# Driver.net
KiCad netlist of a schematic drawn in Altium Designer
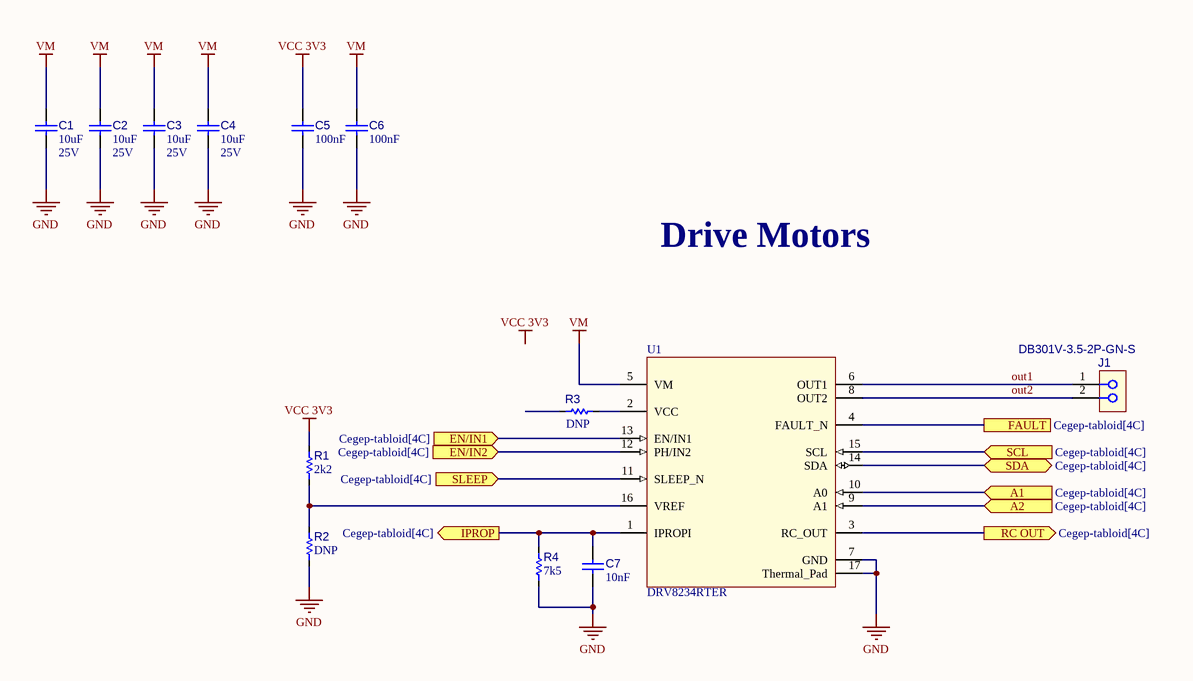
[diagram p0: Driver.SchDoc]

(export (version "E")
  (design (tool "Eeschema 10.0.6"))
  (components
    (comp (ref "C1")
      (value "10uF")
      (footprint "C_2012[0805]")
      (description "Capacitor type 1")
      (fields
        (field (name "TOLERANCE") "10%")
        (field (name "RATED VOLTAGE") "25V")
        (field (name "Comment") "CAP CER 10uF 25V X5R 0805")
      )
      (libsource (lib "243-436-MikoBus-DrvMot") (part "CAP020"))
    )
    (comp (ref "C2")
      (value "10uF")
      (footprint "C_2012[0805]")
      (description "Capacitor type 1")
      (fields
        (field (name "TOLERANCE") "10%")
        (field (name "RATED VOLTAGE") "25V")
        (field (name "Comment") "CAP CER 10uF 25V X5R 0805")
      )
      (libsource (lib "243-436-MikoBus-DrvMot") (part "CAP020"))
    )
    (comp (ref "C3")
      (value "10uF")
      (footprint "C_2012[0805]")
      (description "Capacitor type 1")
      (fields
        (field (name "TOLERANCE") "10%")
        (field (name "RATED VOLTAGE") "25V")
        (field (name "Comment") "CAP CER 10uF 25V X5R 0805")
      )
      (libsource (lib "243-436-MikoBus-DrvMot") (part "CAP020"))
    )
    (comp (ref "C4")
      (value "10uF")
      (footprint "C_2012[0805]")
      (description "Capacitor type 1")
      (fields
        (field (name "TOLERANCE") "10%")
        (field (name "RATED VOLTAGE") "25V")
        (field (name "Comment") "CAP CER 10uF 25V X5R 0805")
      )
      (libsource (lib "243-436-MikoBus-DrvMot") (part "CAP020"))
    )
    (comp (ref "C5")
      (value "100nF")
      (footprint "C_1005[0402]")
      (description "Capacitor type 1")
      (fields (field (name "TOLERANCE") "10%") (field (name "Comment") "CAP CER 100nF 50V 0402"))
      (libsource (lib "243-436-MikoBus-DrvMot") (part "CAP001"))
    )
    (comp (ref "C6")
      (value "100nF")
      (footprint "C_1005[0402]")
      (description "Capacitor type 1")
      (fields (field (name "TOLERANCE") "10%") (field (name "Comment") "CAP CER 100nF 50V 0402"))
      (libsource (lib "243-436-MikoBus-DrvMot") (part "CAP001"))
    )
    (comp (ref "C7")
      (value "10nF")
      (footprint "C_1005[0402]")
      (description "Capacitor type 1")
      (fields (field (name "TOLERANCE") "10%") (field (name "Comment") "CAP CER 10nF 50V X7R 0402"))
      (libsource (lib "243-436-MikoBus-DrvMot") (part "CAP017"))
    )
    (comp (ref "J1")
      (value "DB301V-3.5-2P-GN-S")
      (footprint "CONN_TERM_BLOCK_2POS_3mm5")
      (description "CONN TERM BLOCK 2POS 3.5mm pitch")
      (libsource (lib "TEP_243-AltiumLIB-Conn-TP-MH") (part "CONN-3MM5-2POS-TERM-BLOCK"))
    )
    (comp (ref "R1")
      (value "2k2")
      (footprint "R_1005[0402]")
      (description "Resistor type 1")
      (fields (field (name "TOLERANCE") "1%") (field (name "Comment") "Res 2k2 1% 0402"))
      (libsource (lib "243-436-MikoBus-DrvMot") (part "RES008"))
    )
    (comp (ref "R2")
      (value "DNP")
      (footprint "R_1005[0402]")
      (description "Resistor type 1")
      (fields (field (name "TOLERANCE") "1%") (field (name "Comment") "Res 2k2 1% 0402"))
      (libsource (lib "243-436-MikoBus-DrvMot") (part "RES008"))
    )
    (comp (ref "R3")
      (value "DNP")
      (footprint "R_1005[0402]")
      (description "Resistor type 1")
      (fields (field (name "TOLERANCE") "1%") (field (name "Comment") "Res 2k2 1% 0402"))
      (libsource (lib "243-436-MikoBus-DrvMot") (part "RES008"))
    )
    (comp (ref "R4")
      (value "7k5")
      (footprint "R_1005[0402]")
      (description "Resistor type 1")
      (fields (field (name "TOLERANCE") "1%") (field (name "Comment") "Res 7k5 1% 0402"))
      (libsource (lib "TEP_243-Altium_DBLib") (part "resistor"))
    )
    (comp (ref "U1")
      (value "DRV8234RTER")
      (footprint "U_WQFN50P300X300-16")
      (libsource (lib "TEP_243-Altium_Library") (part "U_DRV8234"))
    )
  )
  (nets
    (net (code "1") (name "/A1") (class "Default")
      (node (ref "U1") (pin "10") (pinfunction "A0_10") (pintype "input"))
    )
    (net (code "2") (name "/A2") (class "Default")
      (node (ref "U1") (pin "9") (pinfunction "A1_9") (pintype "input"))
    )
    (net (code "3") (name "/EN{slash}IN1") (class "Default")
      (node (ref "U1") (pin "13") (pinfunction "EN/IN1_13") (pintype "input"))
    )
    (net (code "4") (name "/EN{slash}IN2") (class "Default")
      (node (ref "U1") (pin "12") (pinfunction "PH/IN2_12") (pintype "input"))
    )
    (net (code "5") (name "/FAULT") (class "Default")
      (node (ref "U1") (pin "4") (pinfunction "FAULT_N_4") (pintype "open_collector"))
    )
    (net (code "6") (name "/IPROP") (class "Default")
      (node (ref "C7") (pin "2") (pinfunction "2_2") (pintype "passive"))
      (node (ref "R4") (pin "1") (pinfunction "1_1") (pintype "passive"))
      (node (ref "U1") (pin "1") (pinfunction "IPROPI_1") (pintype "passive"))
    )
    (net (code "7") (name "/RC OUT") (class "Default")
      (node (ref "U1") (pin "3") (pinfunction "RC_OUT_3") (pintype "open_collector"))
    )
    (net (code "8") (name "/SCL") (class "Default")
      (node (ref "U1") (pin "15") (pinfunction "SCL_15") (pintype "input"))
    )
    (net (code "9") (name "/SDA") (class "Default")
      (node (ref "U1") (pin "14") (pinfunction "SDA_14") (pintype "bidirectional"))
    )
    (net (code "10") (name "/SLEEP") (class "Default")
      (node (ref "U1") (pin "11") (pinfunction "SLEEP_N_11") (pintype "input"))
    )
    (net (code "11") (name "/out1") (class "Default")
      (node (ref "J1") (pin "1") (pinfunction "1_1") (pintype "passive"))
      (node (ref "U1") (pin "6") (pinfunction "OUT1_6") (pintype "passive"))
    )
    (net (code "12") (name "/out2") (class "Default")
      (node (ref "J1") (pin "2") (pinfunction "2_2") (pintype "passive"))
      (node (ref "U1") (pin "8") (pinfunction "OUT2_8") (pintype "passive"))
    )
    (net (code "13") (name "GND") (class "Default")
      (node (ref "C1") (pin "2") (pinfunction "2_2") (pintype "passive"))
      (node (ref "C2") (pin "2") (pinfunction "2_2") (pintype "passive"))
      (node (ref "C3") (pin "2") (pinfunction "2_2") (pintype "passive"))
      (node (ref "C4") (pin "2") (pinfunction "2_2") (pintype "passive"))
      (node (ref "C5") (pin "2") (pinfunction "2_2") (pintype "passive"))
      (node (ref "C6") (pin "2") (pinfunction "2_2") (pintype "passive"))
      (node (ref "C7") (pin "1") (pinfunction "1_1") (pintype "passive"))
      (node (ref "R2") (pin "2") (pinfunction "2_2") (pintype "passive"))
      (node (ref "R4") (pin "2") (pinfunction "2_2") (pintype "passive"))
      (node (ref "U1") (pin "17") (pinfunction "Thermal_Pad_17") (pintype "power_in"))
      (node (ref "U1") (pin "7") (pinfunction "GND_7") (pintype "power_in"))
    )
    (net (code "14") (name "Net-(U1-VCC)") (class "Default")
      (node (ref "R3") (pin "1") (pinfunction "1_1") (pintype "passive"))
      (node (ref "U1") (pin "2") (pinfunction "VCC_2") (pintype "power_in"))
    )
    (net (code "15") (name "Net-(U1-VREF)") (class "Default")
      (node (ref "R1") (pin "2") (pinfunction "2_2") (pintype "passive"))
      (node (ref "R2") (pin "1") (pinfunction "1_1") (pintype "passive"))
      (node (ref "U1") (pin "16") (pinfunction "VREF_16") (pintype "passive"))
    )
    (net (code "16") (name "VCC 3V3") (class "Default")
      (node (ref "C5") (pin "1") (pinfunction "1_1") (pintype "passive"))
      (node (ref "R1") (pin "1") (pinfunction "1_1") (pintype "passive"))
    )
    (net (code "17") (name "VM") (class "Default")
      (node (ref "C1") (pin "1") (pinfunction "1_1") (pintype "passive"))
      (node (ref "C2") (pin "1") (pinfunction "1_1") (pintype "passive"))
      (node (ref "C3") (pin "1") (pinfunction "1_1") (pintype "passive"))
      (node (ref "C4") (pin "1") (pinfunction "1_1") (pintype "passive"))
      (node (ref "C6") (pin "1") (pinfunction "1_1") (pintype "passive"))
      (node (ref "U1") (pin "5") (pinfunction "VM_5") (pintype "power_in"))
    )
    (net (code "18") (name "unconnected-(R3-Pad2)") (class "Default")
      (node (ref "R3") (pin "2") (pinfunction "2_2") (pintype "passive"))
    )
  )
)
